# spad-wirebonding-board.net
KiCad netlist of a schematic drawn in EAGLE
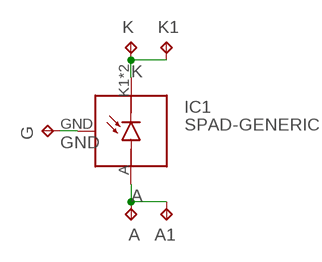
[diagram p0: schematic, sheet 1]

(export (version "E")
  (design (tool "Eeschema 10.0.6"))
  (components
    (comp (ref "A")
      (value "TPTP10R")
      (footprint "eagle-import:TP10R")
      (libsource (lib "eagle-import") (part "TPTP10R"))
    )
    (comp (ref "A1")
      (value "TPTP10R")
      (footprint "eagle-import:TP10R")
      (libsource (lib "eagle-import") (part "TPTP10R"))
    )
    (comp (ref "G")
      (value "TPTP10R")
      (footprint "eagle-import:TP10R")
      (libsource (lib "eagle-import") (part "TPTP10R"))
    )
    (comp (ref "IC1")
      (value "SPAD-GENERIC")
      (footprint "eagle-import:SPAD-WIREBOND-GENERIC-CRYO")
      (libsource (lib "eagle-import") (part "SPAD-GENERIC"))
    )
    (comp (ref "K")
      (value "TPTP10R")
      (footprint "eagle-import:TP10R")
      (libsource (lib "eagle-import") (part "TPTP10R"))
    )
    (comp (ref "K1")
      (value "TPTP10R")
      (footprint "eagle-import:TP10R")
      (libsource (lib "eagle-import") (part "TPTP10R"))
    )
  )
  (nets
    (net (code "1") (name "/A") (class "Default")
      (node (ref "A") (pin "TP") (pinfunction "TP_TP") (pintype "input"))
      (node (ref "A1") (pin "TP") (pinfunction "TP_TP") (pintype "input"))
      (node (ref "IC1") (pin "A") (pinfunction "SPAD_ANODE_A") (pintype "bidirectional"))
    )
    (net (code "2") (name "/GND") (class "Default")
      (node (ref "G") (pin "TP") (pinfunction "TP_TP") (pintype "input"))
      (node (ref "IC1") (pin "GND") (pinfunction "GND_GND") (pintype "bidirectional"))
    )
    (net (code "3") (name "/K") (class "Default")
      (node (ref "IC1") (pin "K1") (pinfunction "SPAD_CATHODE_K1") (pintype "bidirectional"))
      (node (ref "IC1") (pin "K2") (pinfunction "SPAD_CATHODE_K2") (pintype "bidirectional"))
      (node (ref "K") (pin "TP") (pinfunction "TP_TP") (pintype "input"))
      (node (ref "K1") (pin "TP") (pinfunction "TP_TP") (pintype "input"))
    )
  )
)
